# mpu.net
KiCad netlist of a schematic drawn in Altium Designer
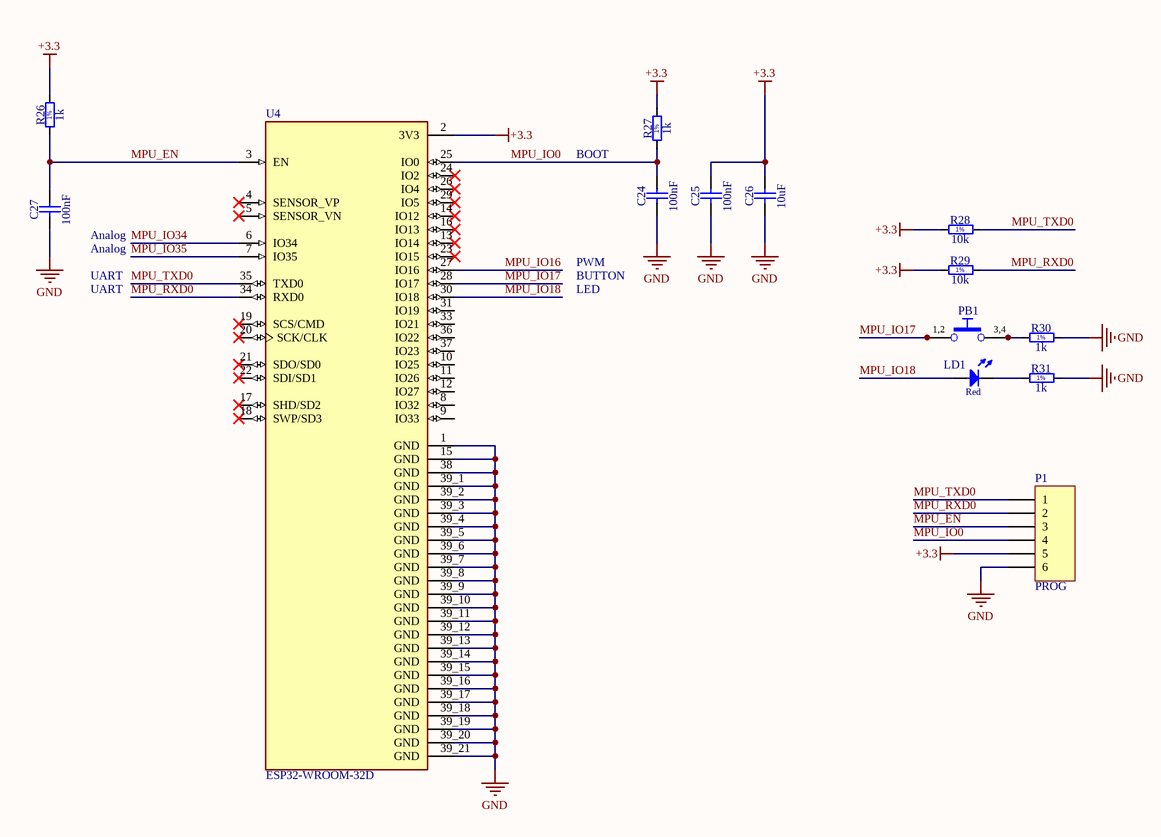
[diagram p0: mpu.SchDoc]

(export (version "E")
  (design (tool "Eeschema 10.0.6"))
  (components
    (comp (ref "C24")
      (value "100nF")
      (footprint "CAPC2012X135N")
      (description "Non-polarised capacitor")
      (fields
        (field (name "PART NUMBER") "CC0805_100NF_50V_10%_X7R")
        (field (name "VOLTAGE") "50V")
        (field (name "AUTHOR") "CERN DEM JLC")
      )
      (libsource (lib "Capacitors") (part "Capacitor - non polarized"))
    )
    (comp (ref "C25")
      (value "100nF")
      (footprint "CAPC2012X135N")
      (description "Non-polarised capacitor")
      (fields
        (field (name "PART NUMBER") "CC0805_100NF_50V_10%_X7R")
        (field (name "VOLTAGE") "50V")
        (field (name "AUTHOR") "CERN DEM JLC")
      )
      (libsource (lib "Capacitors") (part "Capacitor - non polarized"))
    )
    (comp (ref "C26")
      (value "10uF")
      (footprint "CAPC2012X135N")
      (description "Non-polarised capacitor")
      (fields
        (field (name "PART NUMBER") "CC0805_10UF_10V_10%_X7R")
        (field (name "VOLTAGE") "10V")
        (field (name "AUTHOR") "CERN DEM JLC")
      )
      (libsource (lib "Capacitors") (part "Capacitor - non polarized"))
    )
    (comp (ref "C27")
      (value "100nF")
      (footprint "CAPC2012X135N")
      (description "Non-polarised capacitor")
      (fields
        (field (name "PART NUMBER") "CC0805_100NF_50V_10%_X7R")
        (field (name "VOLTAGE") "50V")
        (field (name "AUTHOR") "CERN DEM JLC")
      )
      (libsource (lib "Capacitors") (part "Capacitor - non polarized"))
    )
    (comp (ref "LD1")
      (value "Red")
      (footprint "LED_OSRAM_LHN974")
      (description "LED Red 1C 2A")
      (fields
        (field (name "PART NUMBER") "LED_OSRAM_LHN974")
        (field (name "MANUFACTURER") "OSRAM")
        (field (name "AUTHOR") "CERN DEM JMW")
      )
      (libsource (lib "ICs And Semiconductors") (part "LED Red 1C 2A"))
    )
    (comp (ref "P1")
      (value "PROG")
      (footprint "HDR1X6")
      (description "Header, 6-Pin")
      (fields (field (name "PUBLISHER") "Altium Limited"))
      (libsource (lib "Miscellaneous Connectors") (part "Header 6"))
    )
    (comp (ref "PB1")
      (value "Push Button")
      (footprint "PB_OMRON_B3F-1000")
      (description "Push-Button Switch SPDT")
      (fields
        (field (name "PART NUMBER") "PB_OMRON_B3F-1000")
        (field (name "MANUFACTURER") "OMRON")
        (field (name "AUTHOR") "CERN DEM JMW")
      )
      (libsource (lib "Eletro-mechanical") (part "PB SPST 12NO-34NO"))
    )
    (comp (ref "R26")
      (value "1k")
      (footprint "RESC2012X60N")
      (description "Resistor - 1%")
      (fields
        (field (name "PART NUMBER") "R0805_1K_1%_0.125W_100PPM")
        (field (name "POWER") "0.125W")
        (field (name "AUTHOR") "CERN DEM JLC")
      )
      (libsource (lib "Resistors") (part "Resistor - 1%"))
    )
    (comp (ref "R27")
      (value "1k")
      (footprint "RESC2012X60N")
      (description "Resistor - 1%")
      (fields
        (field (name "PART NUMBER") "R0805_1K_1%_0.125W_100PPM")
        (field (name "POWER") "0.125W")
        (field (name "AUTHOR") "CERN DEM JLC")
      )
      (libsource (lib "Resistors") (part "Resistor - 1%"))
    )
    (comp (ref "R28")
      (value "10k")
      (footprint "RESC2012X60N")
      (description "Resistor - 1%")
      (fields
        (field (name "PART NUMBER") "R0805_10K_1%_0.125W_100PPM")
        (field (name "POWER") "0.125W")
        (field (name "AUTHOR") "CERN DEM JLC")
      )
      (libsource (lib "Resistors") (part "Resistor - 1%"))
    )
    (comp (ref "R29")
      (value "10k")
      (footprint "RESC2012X60N")
      (description "Resistor - 1%")
      (fields
        (field (name "PART NUMBER") "R0805_10K_1%_0.125W_100PPM")
        (field (name "POWER") "0.125W")
        (field (name "AUTHOR") "CERN DEM JLC")
      )
      (libsource (lib "Resistors") (part "Resistor - 1%"))
    )
    (comp (ref "R30")
      (value "1k")
      (footprint "RESC2012X60N")
      (description "Resistor - 1%")
      (fields
        (field (name "PART NUMBER") "R0805_1K_1%_0.125W_100PPM")
        (field (name "POWER") "0.125W")
        (field (name "AUTHOR") "CERN DEM JLC")
      )
      (libsource (lib "Resistors") (part "Resistor - 1%"))
    )
    (comp (ref "R31")
      (value "1k")
      (footprint "RESC2012X60N")
      (description "Resistor - 1%")
      (fields
        (field (name "PART NUMBER") "R0805_1K_1%_0.125W_100PPM")
        (field (name "POWER") "0.125W")
        (field (name "AUTHOR") "CERN DEM JLC")
      )
      (libsource (lib "Resistors") (part "Resistor - 1%"))
    )
    (comp (ref "U4")
      (value "ESP32-WROOM-32D")
      (footprint "ESP32-WROOM-32D:MODULE_ESP32-WROOM-32D")
      (fields (field (name "MF") "Espressif Systems"))
      (libsource (lib "ESP32-WROOM-32D") (part "ESP32-WROOM-32D"))
    )
  )
  (nets
    (net (code "1") (name "+3.3") (class "Default")
      (node (ref "C25") (pin "2") (pinfunction "2_2") (pintype "passive"))
      (node (ref "C26") (pin "2") (pinfunction "2_2") (pintype "passive"))
      (node (ref "P1") (pin "5") (pinfunction "5_5") (pintype "passive"))
      (node (ref "R26") (pin "2") (pinfunction "2_2") (pintype "passive"))
      (node (ref "R27") (pin "2") (pinfunction "2_2") (pintype "passive"))
      (node (ref "R28") (pin "1") (pinfunction "1_1") (pintype "passive"))
      (node (ref "R29") (pin "1") (pinfunction "1_1") (pintype "passive"))
      (node (ref "U4") (pin "2") (pinfunction "3V3_2") (pintype "power_in"))
    )
    (net (code "2") (name "/MPU_EN") (class "Default")
      (node (ref "C27") (pin "2") (pinfunction "2_2") (pintype "passive"))
      (node (ref "P1") (pin "3") (pinfunction "3_3") (pintype "passive"))
      (node (ref "R26") (pin "1") (pinfunction "1_1") (pintype "passive"))
      (node (ref "U4") (pin "3") (pinfunction "EN_3") (pintype "input"))
    )
    (net (code "3") (name "/MPU_IO0") (class "Default")
      (node (ref "C24") (pin "2") (pinfunction "2_2") (pintype "passive"))
      (node (ref "P1") (pin "4") (pinfunction "4_4") (pintype "passive"))
      (node (ref "R27") (pin "1") (pinfunction "1_1") (pintype "passive"))
      (node (ref "U4") (pin "25") (pinfunction "IO0_25") (pintype "bidirectional"))
    )
    (net (code "4") (name "/MPU_IO16") (class "Default")
      (node (ref "U4") (pin "27") (pinfunction "IO16_27") (pintype "bidirectional"))
    )
    (net (code "5") (name "/MPU_IO17") (class "Default")
      (node (ref "PB1") (pin "1") (pinfunction "1_1") (pintype "passive"))
      (node (ref "PB1") (pin "2") (pinfunction "2_2") (pintype "passive"))
      (node (ref "U4") (pin "28") (pinfunction "IO17_28") (pintype "bidirectional"))
    )
    (net (code "6") (name "/MPU_IO18") (class "Default")
      (node (ref "LD1") (pin "2") (pinfunction "A_2") (pintype "passive"))
      (node (ref "U4") (pin "30") (pinfunction "IO18_30") (pintype "bidirectional"))
    )
    (net (code "7") (name "/MPU_IO34") (class "Default")
      (node (ref "U4") (pin "6") (pinfunction "IO34_6") (pintype "input"))
    )
    (net (code "8") (name "/MPU_IO35") (class "Default")
      (node (ref "U4") (pin "7") (pinfunction "IO35_7") (pintype "input"))
    )
    (net (code "9") (name "/MPU_RXD0") (class "Default")
      (node (ref "P1") (pin "2") (pinfunction "2_2") (pintype "passive"))
      (node (ref "R29") (pin "2") (pinfunction "2_2") (pintype "passive"))
      (node (ref "U4") (pin "34") (pinfunction "RXD0_34") (pintype "bidirectional"))
    )
    (net (code "10") (name "/MPU_TXD0") (class "Default")
      (node (ref "P1") (pin "1") (pinfunction "1_1") (pintype "passive"))
      (node (ref "R28") (pin "2") (pinfunction "2_2") (pintype "passive"))
      (node (ref "U4") (pin "35") (pinfunction "TXD0_35") (pintype "bidirectional"))
    )
    (net (code "11") (name "GND") (class "Default")
      (node (ref "C24") (pin "1") (pinfunction "1_1") (pintype "passive"))
      (node (ref "C25") (pin "1") (pinfunction "1_1") (pintype "passive"))
      (node (ref "C26") (pin "1") (pinfunction "1_1") (pintype "passive"))
      (node (ref "C27") (pin "1") (pinfunction "1_1") (pintype "passive"))
      (node (ref "P1") (pin "6") (pinfunction "6_6") (pintype "passive"))
      (node (ref "R30") (pin "2") (pinfunction "2_2") (pintype "passive"))
      (node (ref "R31") (pin "2") (pinfunction "2_2") (pintype "passive"))
      (node (ref "U4") (pin "1") (pinfunction "GND_1") (pintype "power_in"))
      (node (ref "U4") (pin "15") (pinfunction "GND_15") (pintype "power_in"))
      (node (ref "U4") (pin "38") (pinfunction "GND_38") (pintype "power_in"))
      (node (ref "U4") (pin "39_1") (pinfunction "GND_39_1") (pintype "power_in"))
      (node (ref "U4") (pin "39_10") (pinfunction "GND_39_10") (pintype "power_in"))
      (node (ref "U4") (pin "39_11") (pinfunction "GND_39_11") (pintype "power_in"))
      (node (ref "U4") (pin "39_12") (pinfunction "GND_39_12") (pintype "power_in"))
      (node (ref "U4") (pin "39_13") (pinfunction "GND_39_13") (pintype "power_in"))
      (node (ref "U4") (pin "39_14") (pinfunction "GND_39_14") (pintype "power_in"))
      (node (ref "U4") (pin "39_15") (pinfunction "GND_39_15") (pintype "power_in"))
      (node (ref "U4") (pin "39_16") (pinfunction "GND_39_16") (pintype "power_in"))
      (node (ref "U4") (pin "39_17") (pinfunction "GND_39_17") (pintype "power_in"))
      (node (ref "U4") (pin "39_18") (pinfunction "GND_39_18") (pintype "power_in"))
      (node (ref "U4") (pin "39_19") (pinfunction "GND_39_19") (pintype "power_in"))
      (node (ref "U4") (pin "39_2") (pinfunction "GND_39_2") (pintype "power_in"))
      (node (ref "U4") (pin "39_20") (pinfunction "GND_39_20") (pintype "power_in"))
      (node (ref "U4") (pin "39_21") (pinfunction "GND_39_21") (pintype "power_in"))
      (node (ref "U4") (pin "39_3") (pinfunction "GND_39_3") (pintype "power_in"))
      (node (ref "U4") (pin "39_4") (pinfunction "GND_39_4") (pintype "power_in"))
      (node (ref "U4") (pin "39_5") (pinfunction "GND_39_5") (pintype "power_in"))
      (node (ref "U4") (pin "39_6") (pinfunction "GND_39_6") (pintype "power_in"))
      (node (ref "U4") (pin "39_7") (pinfunction "GND_39_7") (pintype "power_in"))
      (node (ref "U4") (pin "39_8") (pinfunction "GND_39_8") (pintype "power_in"))
      (node (ref "U4") (pin "39_9") (pinfunction "GND_39_9") (pintype "power_in"))
    )
    (net (code "12") (name "Net-(LD1-C)") (class "Default")
      (node (ref "LD1") (pin "1") (pinfunction "C_1") (pintype "passive"))
      (node (ref "R31") (pin "1") (pinfunction "1_1") (pintype "passive"))
    )
    (net (code "13") (name "Net-(PB1-Pad3)") (class "Default")
      (node (ref "PB1") (pin "3") (pinfunction "3_3") (pintype "passive"))
      (node (ref "PB1") (pin "4") (pinfunction "4_4") (pintype "passive"))
      (node (ref "R30") (pin "1") (pinfunction "1_1") (pintype "passive"))
    )
    (net (code "14") (name "unconnected-(U4-IO2-Pad24)") (class "Default")
      (node (ref "U4") (pin "24") (pinfunction "IO2_24") (pintype "bidirectional+no_connect"))
    )
    (net (code "15") (name "unconnected-(U4-IO4-Pad26)") (class "Default")
      (node (ref "U4") (pin "26") (pinfunction "IO4_26") (pintype "bidirectional+no_connect"))
    )
    (net (code "16") (name "unconnected-(U4-IO5-Pad29)") (class "Default")
      (node (ref "U4") (pin "29") (pinfunction "IO5_29") (pintype "bidirectional+no_connect"))
    )
    (net (code "17") (name "unconnected-(U4-IO12-Pad14)") (class "Default")
      (node (ref "U4") (pin "14") (pinfunction "IO12_14") (pintype "bidirectional+no_connect"))
    )
    (net (code "18") (name "unconnected-(U4-IO13-Pad16)") (class "Default")
      (node (ref "U4") (pin "16") (pinfunction "IO13_16") (pintype "bidirectional+no_connect"))
    )
    (net (code "19") (name "unconnected-(U4-IO14-Pad13)") (class "Default")
      (node (ref "U4") (pin "13") (pinfunction "IO14_13") (pintype "bidirectional+no_connect"))
    )
    (net (code "20") (name "unconnected-(U4-IO15-Pad23)") (class "Default")
      (node (ref "U4") (pin "23") (pinfunction "IO15_23") (pintype "bidirectional+no_connect"))
    )
    (net (code "21") (name "unconnected-(U4-IO19-Pad31)") (class "Default")
      (node (ref "U4") (pin "31") (pinfunction "IO19_31") (pintype "bidirectional"))
    )
    (net (code "22") (name "unconnected-(U4-IO21-Pad33)") (class "Default")
      (node (ref "U4") (pin "33") (pinfunction "IO21_33") (pintype "bidirectional"))
    )
    (net (code "23") (name "unconnected-(U4-IO22-Pad36)") (class "Default")
      (node (ref "U4") (pin "36") (pinfunction "IO22_36") (pintype "bidirectional"))
    )
    (net (code "24") (name "unconnected-(U4-IO23-Pad37)") (class "Default")
      (node (ref "U4") (pin "37") (pinfunction "IO23_37") (pintype "bidirectional"))
    )
    (net (code "25") (name "unconnected-(U4-IO25-Pad10)") (class "Default")
      (node (ref "U4") (pin "10") (pinfunction "IO25_10") (pintype "bidirectional"))
    )
    (net (code "26") (name "unconnected-(U4-IO26-Pad11)") (class "Default")
      (node (ref "U4") (pin "11") (pinfunction "IO26_11") (pintype "bidirectional"))
    )
    (net (code "27") (name "unconnected-(U4-IO27-Pad12)") (class "Default")
      (node (ref "U4") (pin "12") (pinfunction "IO27_12") (pintype "bidirectional"))
    )
    (net (code "28") (name "unconnected-(U4-IO32-Pad8)") (class "Default")
      (node (ref "U4") (pin "8") (pinfunction "IO32_8") (pintype "bidirectional"))
    )
    (net (code "29") (name "unconnected-(U4-IO33-Pad9)") (class "Default")
      (node (ref "U4") (pin "9") (pinfunction "IO33_9") (pintype "bidirectional"))
    )
    (net (code "30") (name "unconnected-(U4-SCK{slash}CLK-Pad20)") (class "Default")
      (node (ref "U4") (pin "20") (pinfunction "SCK/CLK_20") (pintype "bidirectional+no_connect"))
    )
    (net (code "31") (name "unconnected-(U4-SCS{slash}CMD-Pad19)") (class "Default")
      (node (ref "U4") (pin "19") (pinfunction "SCS/CMD_19") (pintype "bidirectional+no_connect"))
    )
    (net (code "32") (name "unconnected-(U4-SDI{slash}SD1-Pad22)") (class "Default")
      (node (ref "U4") (pin "22") (pinfunction "SDI/SD1_22") (pintype "bidirectional+no_connect"))
    )
    (net (code "33") (name "unconnected-(U4-SDO{slash}SD0-Pad21)") (class "Default")
      (node (ref "U4") (pin "21") (pinfunction "SDO/SD0_21") (pintype "bidirectional+no_connect"))
    )
    (net (code "34") (name "unconnected-(U4-SENSOR_VN-Pad5)") (class "Default")
      (node (ref "U4") (pin "5") (pinfunction "SENSOR_VN_5") (pintype "input+no_connect"))
    )
    (net (code "35") (name "unconnected-(U4-SENSOR_VP-Pad4)") (class "Default")
      (node (ref "U4") (pin "4") (pinfunction "SENSOR_VP_4") (pintype "input+no_connect"))
    )
    (net (code "36") (name "unconnected-(U4-SHD{slash}SD2-Pad17)") (class "Default")
      (node (ref "U4") (pin "17") (pinfunction "SHD/SD2_17") (pintype "bidirectional+no_connect"))
    )
    (net (code "37") (name "unconnected-(U4-SWP{slash}SD3-Pad18)") (class "Default")
      (node (ref "U4") (pin "18") (pinfunction "SWP/SD3_18") (pintype "bidirectional+no_connect"))
    )
  )
)
